# pure_midi.net
KiCad netlist of a schematic drawn in EAGLE
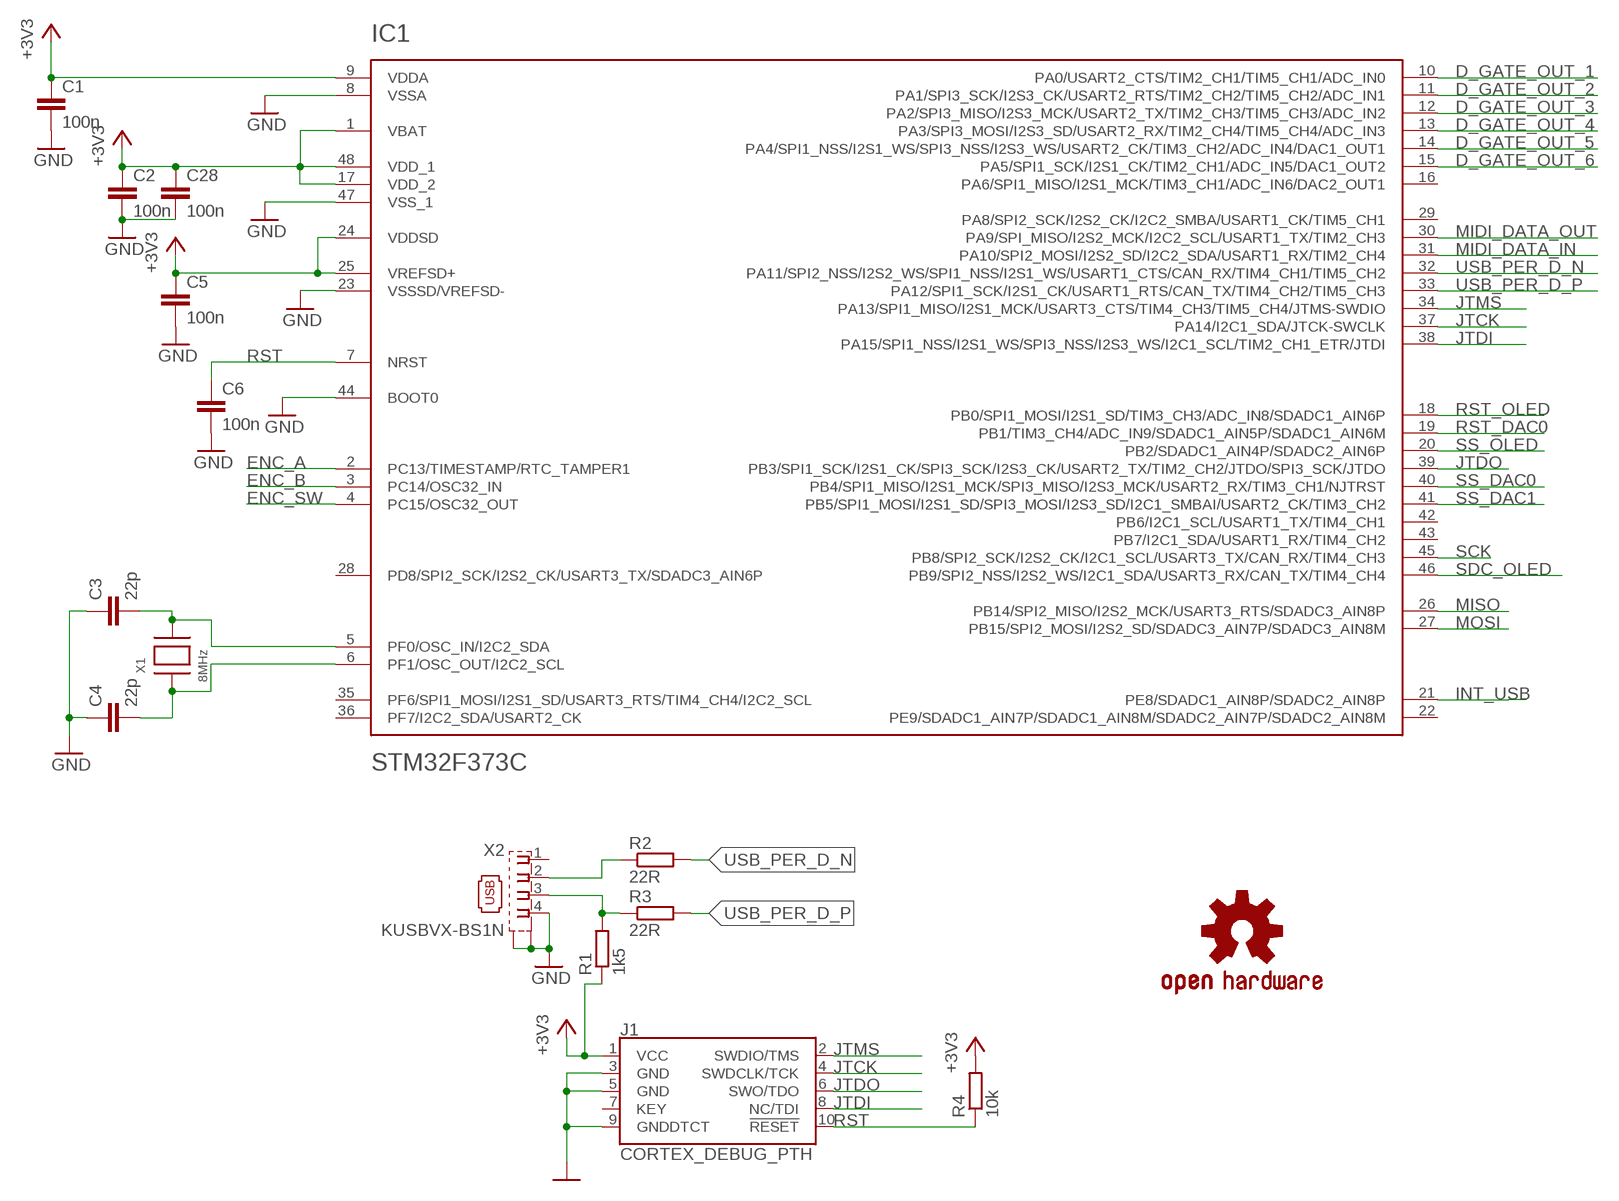
[diagram p0: schematic, sheet 1]
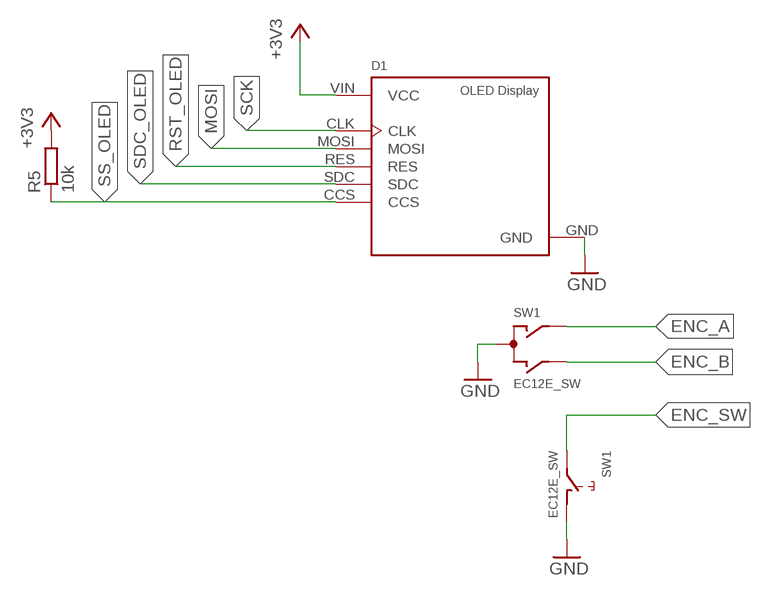
[diagram p1: schematic, sheet 2]
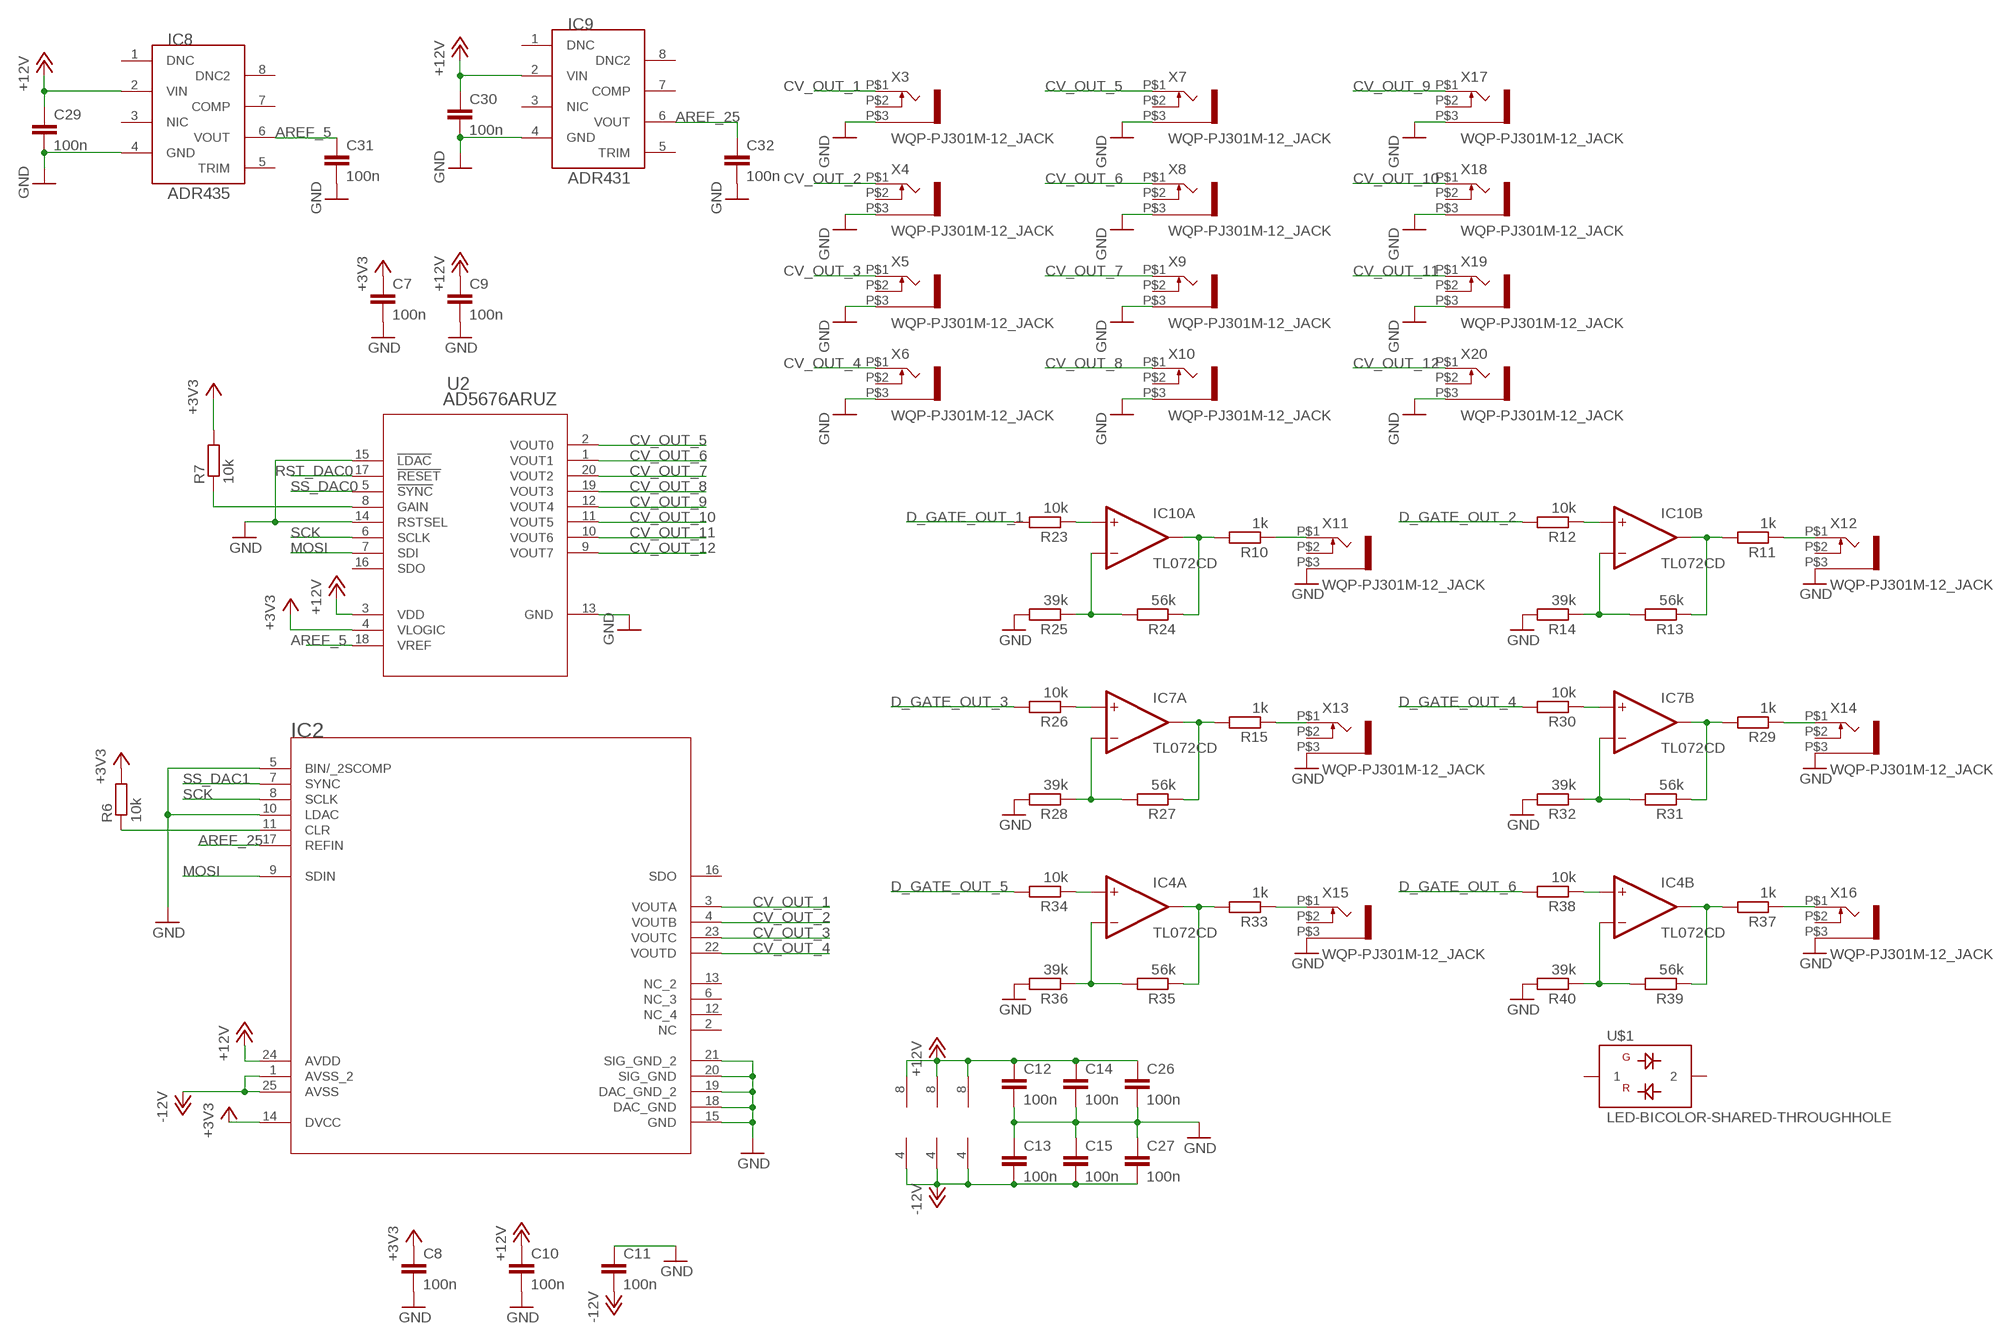
[diagram p2: schematic, sheet 3]
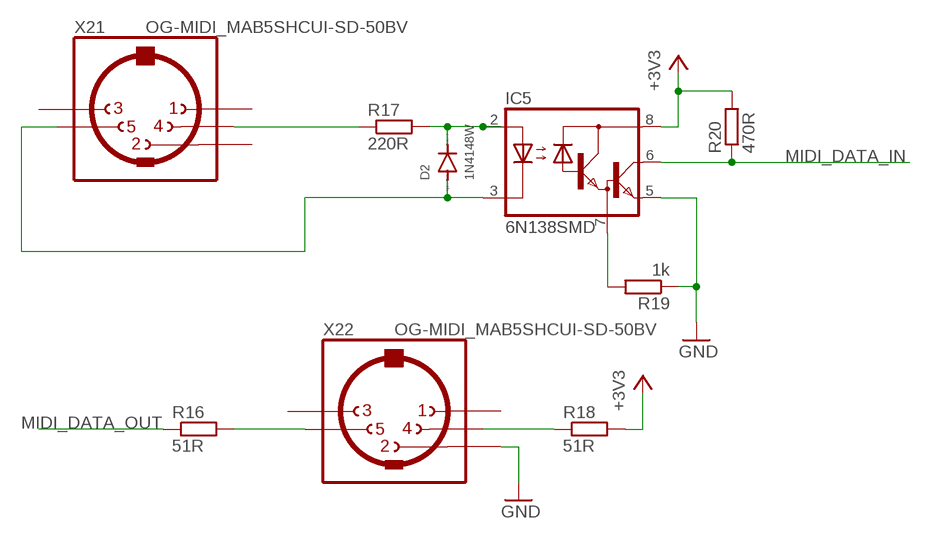
[diagram p3: schematic, sheet 4]
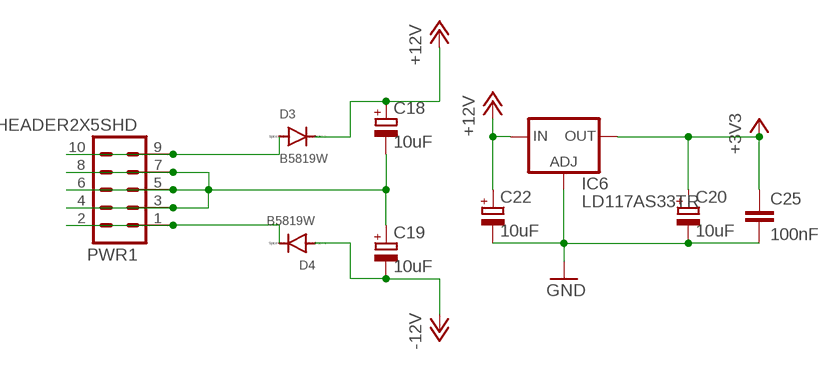
[diagram p4: schematic, sheet 5]

(export (version "E")
  (design (tool "Eeschema 10.0.6"))
  (components
    (comp (ref "C7")
      (value "100n")
      (footprint "eagle-import:C0603")
      (libsource (lib "eagle-import") (part "C-EUC0603"))
    )
    (comp (ref "C8")
      (value "100n")
      (footprint "eagle-import:C0603")
      (libsource (lib "eagle-import") (part "C-EUC0603"))
    )
    (comp (ref "C9")
      (value "100n")
      (footprint "eagle-import:C0603")
      (libsource (lib "eagle-import") (part "C-EUC0603"))
    )
    (comp (ref "C10")
      (value "100n")
      (footprint "eagle-import:C0603")
      (libsource (lib "eagle-import") (part "C-EUC0603"))
    )
    (comp (ref "C11")
      (value "100n")
      (footprint "eagle-import:C0603")
      (libsource (lib "eagle-import") (part "C-EUC0603"))
    )
    (comp (ref "C12")
      (value "100n")
      (footprint "eagle-import:C0603")
      (libsource (lib "eagle-import") (part "C-EUC0603"))
    )
    (comp (ref "C13")
      (value "100n")
      (footprint "eagle-import:C0603")
      (libsource (lib "eagle-import") (part "C-EUC0603"))
    )
    (comp (ref "C14")
      (value "100n")
      (footprint "eagle-import:C0603")
      (libsource (lib "eagle-import") (part "C-EUC0603"))
    )
    (comp (ref "C15")
      (value "100n")
      (footprint "eagle-import:C0603")
      (libsource (lib "eagle-import") (part "C-EUC0603"))
    )
    (comp (ref "C26")
      (value "100n")
      (footprint "eagle-import:C0603")
      (libsource (lib "eagle-import") (part "C-EUC0603"))
    )
    (comp (ref "C27")
      (value "100n")
      (footprint "eagle-import:C0603")
      (libsource (lib "eagle-import") (part "C-EUC0603"))
    )
    (comp (ref "C29")
      (value "100n")
      (footprint "eagle-import:C0603")
      (libsource (lib "eagle-import") (part "C-EUC0603"))
    )
    (comp (ref "C30")
      (value "100n")
      (footprint "eagle-import:C0603")
      (libsource (lib "eagle-import") (part "C-EUC0603"))
    )
    (comp (ref "C31")
      (value "100n")
      (footprint "eagle-import:C0603")
      (libsource (lib "eagle-import") (part "C-EUC0603"))
    )
    (comp (ref "C32")
      (value "100n")
      (footprint "eagle-import:C0603")
      (libsource (lib "eagle-import") (part "C-EUC0603"))
    )
    (comp (ref "IC2")
      (value "AD5754BREZ")
      (footprint "eagle-import:RE_24")
      (libsource (lib "eagle-import") (part "AD5754BREZ"))
    )
    (comp (ref "IC4")
      (value "TL072CD")
      (footprint "eagle-import:SOIC8")
      (libsource (lib "eagle-import") (part "TL072DC"))
    )
    (comp (ref "IC7")
      (value "TL072CD")
      (footprint "eagle-import:SOIC8")
      (libsource (lib "eagle-import") (part "TL072DC"))
    )
    (comp (ref "IC8")
      (value "ADR435")
      (footprint "eagle-import:MSOP8")
      (libsource (lib "eagle-import") (part "ADR43XXRMZ"))
    )
    (comp (ref "IC9")
      (value "ADR431")
      (footprint "eagle-import:MSOP8")
      (libsource (lib "eagle-import") (part "ADR43XXRMZ"))
    )
    (comp (ref "IC10")
      (value "TL072CD")
      (footprint "eagle-import:SOIC8")
      (libsource (lib "eagle-import") (part "TL072DC"))
    )
    (comp (ref "R6")
      (value "10k")
      (footprint "eagle-import:R0603")
      (libsource (lib "eagle-import") (part "R-EU_R0603"))
    )
    (comp (ref "R7")
      (value "10k")
      (footprint "eagle-import:R0603")
      (libsource (lib "eagle-import") (part "R-EU_R0603"))
    )
    (comp (ref "R10")
      (value "1k")
      (footprint "eagle-import:R0603")
      (libsource (lib "eagle-import") (part "R-EU_R0603"))
    )
    (comp (ref "R11")
      (value "1k")
      (footprint "eagle-import:R0603")
      (libsource (lib "eagle-import") (part "R-EU_R0603"))
    )
    (comp (ref "R12")
      (value "10k")
      (footprint "eagle-import:R0603")
      (libsource (lib "eagle-import") (part "R-EU_R0603"))
    )
    (comp (ref "R13")
      (value "56k")
      (footprint "eagle-import:R0603")
      (libsource (lib "eagle-import") (part "R-EU_R0603"))
    )
    (comp (ref "R14")
      (value "39k")
      (footprint "eagle-import:R0603")
      (libsource (lib "eagle-import") (part "R-EU_R0603"))
    )
    (comp (ref "R15")
      (value "1k")
      (footprint "eagle-import:R0603")
      (libsource (lib "eagle-import") (part "R-EU_R0603"))
    )
    (comp (ref "R23")
      (value "10k")
      (footprint "eagle-import:R0603")
      (libsource (lib "eagle-import") (part "R-EU_R0603"))
    )
    (comp (ref "R24")
      (value "56k")
      (footprint "eagle-import:R0603")
      (libsource (lib "eagle-import") (part "R-EU_R0603"))
    )
    (comp (ref "R25")
      (value "39k")
      (footprint "eagle-import:R0603")
      (libsource (lib "eagle-import") (part "R-EU_R0603"))
    )
    (comp (ref "R26")
      (value "10k")
      (footprint "eagle-import:R0603")
      (libsource (lib "eagle-import") (part "R-EU_R0603"))
    )
    (comp (ref "R27")
      (value "56k")
      (footprint "eagle-import:R0603")
      (libsource (lib "eagle-import") (part "R-EU_R0603"))
    )
    (comp (ref "R28")
      (value "39k")
      (footprint "eagle-import:R0603")
      (libsource (lib "eagle-import") (part "R-EU_R0603"))
    )
    (comp (ref "R29")
      (value "1k")
      (footprint "eagle-import:R0603")
      (libsource (lib "eagle-import") (part "R-EU_R0603"))
    )
    (comp (ref "R30")
      (value "10k")
      (footprint "eagle-import:R0603")
      (libsource (lib "eagle-import") (part "R-EU_R0603"))
    )
    (comp (ref "R31")
      (value "56k")
      (footprint "eagle-import:R0603")
      (libsource (lib "eagle-import") (part "R-EU_R0603"))
    )
    (comp (ref "R32")
      (value "39k")
      (footprint "eagle-import:R0603")
      (libsource (lib "eagle-import") (part "R-EU_R0603"))
    )
    (comp (ref "R33")
      (value "1k")
      (footprint "eagle-import:R0603")
      (libsource (lib "eagle-import") (part "R-EU_R0603"))
    )
    (comp (ref "R34")
      (value "10k")
      (footprint "eagle-import:R0603")
      (libsource (lib "eagle-import") (part "R-EU_R0603"))
    )
    (comp (ref "R35")
      (value "56k")
      (footprint "eagle-import:R0603")
      (libsource (lib "eagle-import") (part "R-EU_R0603"))
    )
    (comp (ref "R36")
      (value "39k")
      (footprint "eagle-import:R0603")
      (libsource (lib "eagle-import") (part "R-EU_R0603"))
    )
    (comp (ref "R37")
      (value "1k")
      (footprint "eagle-import:R0603")
      (libsource (lib "eagle-import") (part "R-EU_R0603"))
    )
    (comp (ref "R38")
      (value "10k")
      (footprint "eagle-import:R0603")
      (libsource (lib "eagle-import") (part "R-EU_R0603"))
    )
    (comp (ref "R39")
      (value "56k")
      (footprint "eagle-import:R0603")
      (libsource (lib "eagle-import") (part "R-EU_R0603"))
    )
    (comp (ref "R40")
      (value "39k")
      (footprint "eagle-import:R0603")
      (libsource (lib "eagle-import") (part "R-EU_R0603"))
    )
    (comp (ref "U$1")
      (value "LED-BICOLOR-SHARED-THROUGHHOLE")
      (footprint "eagle-import:LED3MM")
      (libsource (lib "eagle-import") (part "LED-BICOLOR-SHARED-THROUGHHOLE"))
    )
    (comp (ref "U2")
      (value "AD5676ARUZ")
      (footprint "eagle-import:RU_20")
      (libsource (lib "eagle-import") (part "AD5676ARUZ"))
    )
    (comp (ref "X3")
      (value "WQP-PJ301M-12_JACK")
      (footprint "eagle-import:WQP-PJ301M-12_JACK")
      (libsource (lib "eagle-import") (part "WQP-PJ301M-12_JACK"))
    )
    (comp (ref "X4")
      (value "WQP-PJ301M-12_JACK")
      (footprint "eagle-import:WQP-PJ301M-12_JACK")
      (libsource (lib "eagle-import") (part "WQP-PJ301M-12_JACK"))
    )
    (comp (ref "X5")
      (value "WQP-PJ301M-12_JACK")
      (footprint "eagle-import:WQP-PJ301M-12_JACK")
      (libsource (lib "eagle-import") (part "WQP-PJ301M-12_JACK"))
    )
    (comp (ref "X6")
      (value "WQP-PJ301M-12_JACK")
      (footprint "eagle-import:WQP-PJ301M-12_JACK")
      (libsource (lib "eagle-import") (part "WQP-PJ301M-12_JACK"))
    )
    (comp (ref "X7")
      (value "WQP-PJ301M-12_JACK")
      (footprint "eagle-import:WQP-PJ301M-12_JACK")
      (libsource (lib "eagle-import") (part "WQP-PJ301M-12_JACK"))
    )
    (comp (ref "X8")
      (value "WQP-PJ301M-12_JACK")
      (footprint "eagle-import:WQP-PJ301M-12_JACK")
      (libsource (lib "eagle-import") (part "WQP-PJ301M-12_JACK"))
    )
    (comp (ref "X9")
      (value "WQP-PJ301M-12_JACK")
      (footprint "eagle-import:WQP-PJ301M-12_JACK")
      (libsource (lib "eagle-import") (part "WQP-PJ301M-12_JACK"))
    )
    (comp (ref "X10")
      (value "WQP-PJ301M-12_JACK")
      (footprint "eagle-import:WQP-PJ301M-12_JACK")
      (libsource (lib "eagle-import") (part "WQP-PJ301M-12_JACK"))
    )
    (comp (ref "X11")
      (value "WQP-PJ301M-12_JACK")
      (footprint "eagle-import:WQP-PJ301M-12_JACK")
      (libsource (lib "eagle-import") (part "WQP-PJ301M-12_JACK"))
    )
    (comp (ref "X12")
      (value "WQP-PJ301M-12_JACK")
      (footprint "eagle-import:WQP-PJ301M-12_JACK")
      (libsource (lib "eagle-import") (part "WQP-PJ301M-12_JACK"))
    )
    (comp (ref "X13")
      (value "WQP-PJ301M-12_JACK")
      (footprint "eagle-import:WQP-PJ301M-12_JACK")
      (libsource (lib "eagle-import") (part "WQP-PJ301M-12_JACK"))
    )
    (comp (ref "X14")
      (value "WQP-PJ301M-12_JACK")
      (footprint "eagle-import:WQP-PJ301M-12_JACK")
      (libsource (lib "eagle-import") (part "WQP-PJ301M-12_JACK"))
    )
    (comp (ref "X15")
      (value "WQP-PJ301M-12_JACK")
      (footprint "eagle-import:WQP-PJ301M-12_JACK")
      (libsource (lib "eagle-import") (part "WQP-PJ301M-12_JACK"))
    )
    (comp (ref "X16")
      (value "WQP-PJ301M-12_JACK")
      (footprint "eagle-import:WQP-PJ301M-12_JACK")
      (libsource (lib "eagle-import") (part "WQP-PJ301M-12_JACK"))
    )
    (comp (ref "X17")
      (value "WQP-PJ301M-12_JACK")
      (footprint "eagle-import:WQP-PJ301M-12_JACK")
      (libsource (lib "eagle-import") (part "WQP-PJ301M-12_JACK"))
    )
    (comp (ref "X18")
      (value "WQP-PJ301M-12_JACK")
      (footprint "eagle-import:WQP-PJ301M-12_JACK")
      (libsource (lib "eagle-import") (part "WQP-PJ301M-12_JACK"))
    )
    (comp (ref "X19")
      (value "WQP-PJ301M-12_JACK")
      (footprint "eagle-import:WQP-PJ301M-12_JACK")
      (libsource (lib "eagle-import") (part "WQP-PJ301M-12_JACK"))
    )
    (comp (ref "X20")
      (value "WQP-PJ301M-12_JACK")
      (footprint "eagle-import:WQP-PJ301M-12_JACK")
      (libsource (lib "eagle-import") (part "WQP-PJ301M-12_JACK"))
    )
    (comp (ref "C1")
      (value "100n")
      (footprint "eagle-import:C0603")
      (libsource (lib "eagle-import") (part "C-EUC0603"))
    )
    (comp (ref "C2")
      (value "100n")
      (footprint "eagle-import:C0603")
      (libsource (lib "eagle-import") (part "C-EUC0603"))
    )
    (comp (ref "C3")
      (value "22p")
      (footprint "eagle-import:C0603")
      (libsource (lib "eagle-import") (part "C-EUC0603"))
    )
    (comp (ref "C4")
      (value "22p")
      (footprint "eagle-import:C0603")
      (libsource (lib "eagle-import") (part "C-EUC0603"))
    )
    (comp (ref "C5")
      (value "100n")
      (footprint "eagle-import:C0603")
      (libsource (lib "eagle-import") (part "C-EUC0603"))
    )
    (comp (ref "C6")
      (value "100n")
      (footprint "eagle-import:C0603")
      (libsource (lib "eagle-import") (part "C-EUC0603"))
    )
    (comp (ref "C28")
      (value "100n")
      (footprint "eagle-import:C0603")
      (libsource (lib "eagle-import") (part "C-EUC0603"))
    )
    (comp (ref "IC1")
      (value "STM32F373C")
      (footprint "eagle-import:LQFP48")
      (libsource (lib "eagle-import") (part "STM32F373C"))
    )
    (comp (ref "J1")
      (value "CORTEX_DEBUG_PTH")
      (footprint "eagle-import:2X5-PTH-1.27MM")
      (libsource (lib "eagle-import") (part "CORTEX_DEBUG_PTH"))
    )
    (comp (ref "LOGO1")
      (value "OSHW-LOGOM")
      (footprint "eagle-import:OSHW-LOGO-M")
      (libsource (lib "eagle-import") (part "OSHW-LOGOM"))
    )
    (comp (ref "R1")
      (value "1k5")
      (footprint "eagle-import:R0603")
      (libsource (lib "eagle-import") (part "R-EU_R0603"))
    )
    (comp (ref "R2")
      (value "22R")
      (footprint "eagle-import:R0603")
      (libsource (lib "eagle-import") (part "R-EU_R0603"))
    )
    (comp (ref "R3")
      (value "22R")
      (footprint "eagle-import:R0603")
      (libsource (lib "eagle-import") (part "R-EU_R0603"))
    )
    (comp (ref "R4")
      (value "10k")
      (footprint "eagle-import:R0603")
      (libsource (lib "eagle-import") (part "R-EU_R0603"))
    )
    (comp (ref "X1")
      (value "8MHz")
      (footprint "eagle-import:NX5032")
      (libsource (lib "eagle-import") (part "XTALNX5032"))
    )
    (comp (ref "X2")
      (value "KUSBVX-BS1N")
      (footprint "eagle-import:KUSBVX-BS1N")
      (libsource (lib "eagle-import") (part "KUSBVX-BS1N"))
    )
    (comp (ref "D2")
      (value "1N4148W")
      (footprint "eagle-import:SOD123")
      (libsource (lib "eagle-import") (part "DIODE-SOD123"))
    )
    (comp (ref "IC5")
      (value "6N138SMD")
      (footprint "eagle-import:SO8-GW300")
      (libsource (lib "eagle-import") (part "6N138SMD"))
    )
    (comp (ref "R16")
      (value "51R")
      (footprint "eagle-import:R0603")
      (libsource (lib "eagle-import") (part "R-EU_R0603"))
    )
    (comp (ref "R17")
      (value "220R")
      (footprint "eagle-import:R0603")
      (libsource (lib "eagle-import") (part "R-EU_R0603"))
    )
    (comp (ref "R18")
      (value "51R")
      (footprint "eagle-import:R0603")
      (libsource (lib "eagle-import") (part "R-EU_R0603"))
    )
    (comp (ref "R19")
      (value "1k")
      (footprint "eagle-import:R0603")
      (libsource (lib "eagle-import") (part "R-EU_R0603"))
    )
    (comp (ref "R20")
      (value "470R")
      (footprint "eagle-import:R0603")
      (libsource (lib "eagle-import") (part "R-EU_R0603"))
    )
    (comp (ref "X21")
      (value "OG-MIDI_MAB5SHCUI-SD-50BV")
      (footprint "eagle-import:OG-MIDI_SD-50BV")
      (libsource (lib "eagle-import") (part "OG-MIDI_MAB5SHCUI-SD-50BV"))
    )
    (comp (ref "X22")
      (value "OG-MIDI_MAB5SHCUI-SD-50BV")
      (footprint "eagle-import:OG-MIDI_SD-50BV")
      (libsource (lib "eagle-import") (part "OG-MIDI_MAB5SHCUI-SD-50BV"))
    )
    (comp (ref "D1")
      (value "OLED_1.3_128X64_SPI")
      (footprint "eagle-import:C1_ADAFRUIT_1.3_128X64_OLED")
      (libsource (lib "eagle-import") (part "OLED_1.3_128X64_SPI"))
    )
    (comp (ref "R5")
      (value "10k")
      (footprint "eagle-import:R0603")
      (libsource (lib "eagle-import") (part "R-EU_R0603"))
    )
    (comp (ref "SW1")
      (value "EC12E_SW")
      (footprint "eagle-import:ALPS_EC12E_SW")
      (fields (field (name "MPN") "EC12E2424407"))
      (libsource (lib "eagle-import") (part "EC12E_SW"))
    )
    (comp (ref "C18")
      (value "10uF")
      (footprint "eagle-import:CASE-A_3216")
      (libsource (lib "eagle-import") (part "CPOL-EUA/3216-18R"))
    )
    (comp (ref "C19")
      (value "10uF")
      (footprint "eagle-import:CASE-A_3216")
      (libsource (lib "eagle-import") (part "CPOL-EUA/3216-18R"))
    )
    (comp (ref "C20")
      (value "10uF")
      (footprint "eagle-import:CASE-A_3216")
      (libsource (lib "eagle-import") (part "CPOL-EUA/3216-18R"))
    )
    (comp (ref "C22")
      (value "10uF")
      (footprint "eagle-import:CASE-A_3216")
      (libsource (lib "eagle-import") (part "CPOL-EUA/3216-18R"))
    )
    (comp (ref "C25")
      (value "100nF")
      (footprint "eagle-import:C0603")
      (libsource (lib "eagle-import") (part "C-EUC0603"))
    )
    (comp (ref "D3")
      (value "B5819W")
      (footprint "eagle-import:SOD123")
      (libsource (lib "eagle-import") (part "DIODE-SOD123"))
    )
    (comp (ref "D4")
      (value "B5819W")
      (footprint "eagle-import:SOD123")
      (libsource (lib "eagle-import") (part "DIODE-SOD123"))
    )
    (comp (ref "IC6")
      (value "LD117AS33TR")
      (footprint "eagle-import:SOT223")
      (libsource (lib "eagle-import") (part "LD117A?S33TR"))
    )
    (comp (ref "PWR1")
      (value "HEADER2X5SHD")
      (footprint "eagle-import:2X5-SHROUDED")
      (libsource (lib "eagle-import") (part "HEADER2X5SHD"))
    )
  )
  (nets
    (net (code "1") (name "+3V3") (class "Default")
      (node (ref "C1") (pin "1") (pinfunction "1_1") (pintype "passive"))
      (node (ref "C2") (pin "1") (pinfunction "1_1") (pintype "passive"))
      (node (ref "C20") (pin "+") (pinfunction "+_+") (pintype "passive"))
      (node (ref "C25") (pin "1") (pinfunction "1_1") (pintype "passive"))
      (node (ref "C28") (pin "1") (pinfunction "1_1") (pintype "passive"))
      (node (ref "C5") (pin "1") (pinfunction "1_1") (pintype "passive"))
      (node (ref "C7") (pin "1") (pinfunction "1_1") (pintype "passive"))
      (node (ref "C8") (pin "1") (pinfunction "1_1") (pintype "passive"))
      (node (ref "D1") (pin "VIN") (pinfunction "VCC_VIN") (pintype "power_in"))
      (node (ref "IC1") (pin "1") (pinfunction "VBAT_1") (pintype "power_in"))
      (node (ref "IC1") (pin "17") (pinfunction "VDD_2_17") (pintype "power_in"))
      (node (ref "IC1") (pin "24") (pinfunction "VDDSD_24") (pintype "power_in"))
      (node (ref "IC1") (pin "25") (pinfunction "VREFSD+_25") (pintype "power_in"))
      (node (ref "IC1") (pin "48") (pinfunction "VDD_1_48") (pintype "power_in"))
      (node (ref "IC1") (pin "9") (pinfunction "VDDA_9") (pintype "power_in"))
      (node (ref "IC2") (pin "14") (pinfunction "DVCC_14") (pintype "power_in"))
      (node (ref "IC5") (pin "8") (pinfunction "VCC_8") (pintype "passive"))
      (node (ref "IC6") (pin "4") (pinfunction "OUT_4") (pintype "passive"))
      (node (ref "J1") (pin "1") (pinfunction "VCC_1") (pintype "bidirectional"))
      (node (ref "R1") (pin "1") (pinfunction "1_1") (pintype "passive"))
      (node (ref "R18") (pin "2") (pinfunction "2_2") (pintype "passive"))
      (node (ref "R20") (pin "2") (pinfunction "2_2") (pintype "passive"))
      (node (ref "R4") (pin "2") (pinfunction "2_2") (pintype "passive"))
      (node (ref "R5") (pin "2") (pinfunction "2_2") (pintype "passive"))
      (node (ref "R6") (pin "2") (pinfunction "2_2") (pintype "passive"))
      (node (ref "R7") (pin "2") (pinfunction "2_2") (pintype "passive"))
      (node (ref "U2") (pin "4") (pinfunction "VLOGIC_4") (pintype "passive"))
    )
    (net (code "2") (name "+12V") (class "Default")
      (node (ref "C10") (pin "1") (pinfunction "1_1") (pintype "passive"))
      (node (ref "C12") (pin "1") (pinfunction "1_1") (pintype "passive"))
      (node (ref "C14") (pin "1") (pinfunction "1_1") (pintype "passive"))
      (node (ref "C18") (pin "+") (pinfunction "+_+") (pintype "passive"))
      (node (ref "C22") (pin "+") (pinfunction "+_+") (pintype "passive"))
      (node (ref "C26") (pin "1") (pinfunction "1_1") (pintype "passive"))
      (node (ref "C29") (pin "1") (pinfunction "1_1") (pintype "passive"))
      (node (ref "C30") (pin "1") (pinfunction "1_1") (pintype "passive"))
      (node (ref "C9") (pin "1") (pinfunction "1_1") (pintype "passive"))
      (node (ref "D3") (pin "C") (pinfunction "C_C") (pintype "passive"))
      (node (ref "IC10") (pin "8") (pinfunction "V+_8") (pintype "power_in"))
      (node (ref "IC2") (pin "24") (pinfunction "AVDD_24") (pintype "power_in"))
      (node (ref "IC4") (pin "8") (pinfunction "V+_8") (pintype "power_in"))
      (node (ref "IC6") (pin "3") (pinfunction "IN_3") (pintype "input"))
      (node (ref "IC7") (pin "8") (pinfunction "V+_8") (pintype "power_in"))
      (node (ref "IC8") (pin "2") (pinfunction "VIN_2") (pintype "power_in"))
      (node (ref "IC9") (pin "2") (pinfunction "VIN_2") (pintype "power_in"))
      (node (ref "U2") (pin "3") (pinfunction "VDD_3") (pintype "passive"))
    )
    (net (code "3") (name "-12V") (class "Default")
      (node (ref "C11") (pin "2") (pinfunction "2_2") (pintype "passive"))
      (node (ref "C13") (pin "2") (pinfunction "2_2") (pintype "passive"))
      (node (ref "C15") (pin "2") (pinfunction "2_2") (pintype "passive"))
      (node (ref "C19") (pin "-") (pinfunction "-_-") (pintype "passive"))
      (node (ref "C27") (pin "2") (pinfunction "2_2") (pintype "passive"))
      (node (ref "D4") (pin "A") (pinfunction "A_A") (pintype "passive"))
      (node (ref "IC10") (pin "4") (pinfunction "V-_4") (pintype "power_in"))
      (node (ref "IC2") (pin "1") (pinfunction "AVSS_2_1") (pintype "passive"))
      (node (ref "IC2") (pin "25") (pinfunction "AVSS_25") (pintype "power_in"))
      (node (ref "IC4") (pin "4") (pinfunction "V-_4") (pintype "power_in"))
      (node (ref "IC7") (pin "4") (pinfunction "V-_4") (pintype "power_in"))
    )
    (net (code "4") (name "AREF_5") (class "Default")
      (node (ref "C31") (pin "1") (pinfunction "1_1") (pintype "passive"))
      (node (ref "IC8") (pin "6") (pinfunction "VOUT_6") (pintype "power_in"))
      (node (ref "U2") (pin "18") (pinfunction "VREF_18") (pintype "passive"))
    )
    (net (code "5") (name "AREF_25") (class "Default")
      (node (ref "C32") (pin "1") (pinfunction "1_1") (pintype "passive"))
      (node (ref "IC2") (pin "17") (pinfunction "REFIN_17") (pintype "passive"))
      (node (ref "IC9") (pin "6") (pinfunction "VOUT_6") (pintype "power_in"))
    )
    (net (code "6") (name "CV_OUT_1") (class "Default")
      (node (ref "IC2") (pin "3") (pinfunction "VOUTA_3") (pintype "passive"))
      (node (ref "X3") (pin "P$1") (pinfunction "2_P$1") (pintype "passive"))
    )
    (net (code "7") (name "CV_OUT_2") (class "Default")
      (node (ref "IC2") (pin "4") (pinfunction "VOUTB_4") (pintype "passive"))
      (node (ref "X4") (pin "P$1") (pinfunction "2_P$1") (pintype "passive"))
    )
    (net (code "8") (name "CV_OUT_3") (class "Default")
      (node (ref "IC2") (pin "23") (pinfunction "VOUTC_23") (pintype "passive"))
      (node (ref "X5") (pin "P$1") (pinfunction "2_P$1") (pintype "passive"))
    )
    (net (code "9") (name "CV_OUT_4") (class "Default")
      (node (ref "IC2") (pin "22") (pinfunction "VOUTD_22") (pintype "passive"))
      (node (ref "X6") (pin "P$1") (pinfunction "2_P$1") (pintype "passive"))
    )
    (net (code "10") (name "CV_OUT_5") (class "Default")
      (node (ref "U2") (pin "2") (pinfunction "VOUT0_2") (pintype "passive"))
      (node (ref "X7") (pin "P$1") (pinfunction "2_P$1") (pintype "passive"))
    )
    (net (code "11") (name "CV_OUT_6") (class "Default")
      (node (ref "U2") (pin "1") (pinfunction "VOUT1_1") (pintype "passive"))
      (node (ref "X8") (pin "P$1") (pinfunction "2_P$1") (pintype "passive"))
    )
    (net (code "12") (name "CV_OUT_7") (class "Default")
      (node (ref "U2") (pin "20") (pinfunction "VOUT2_20") (pintype "passive"))
      (node (ref "X9") (pin "P$1") (pinfunction "2_P$1") (pintype "passive"))
    )
    (net (code "13") (name "CV_OUT_8") (class "Default")
      (node (ref "U2") (pin "19") (pinfunction "VOUT3_19") (pintype "passive"))
      (node (ref "X10") (pin "P$1") (pinfunction "2_P$1") (pintype "passive"))
    )
    (net (code "14") (name "CV_OUT_9") (class "Default")
      (node (ref "U2") (pin "12") (pinfunction "VOUT4_12") (pintype "passive"))
      (node (ref "X17") (pin "P$1") (pinfunction "2_P$1") (pintype "passive"))
    )
    (net (code "15") (name "CV_OUT_10") (class "Default")
      (node (ref "U2") (pin "11") (pinfunction "VOUT5_11") (pintype "passive"))
      (node (ref "X18") (pin "P$1") (pinfunction "2_P$1") (pintype "passive"))
    )
    (net (code "16") (name "CV_OUT_11") (class "Default")
      (node (ref "U2") (pin "10") (pinfunction "VOUT6_10") (pintype "passive"))
      (node (ref "X19") (pin "P$1") (pinfunction "2_P$1") (pintype "passive"))
    )
    (net (code "17") (name "CV_OUT_12") (class "Default")
      (node (ref "U2") (pin "9") (pinfunction "VOUT7_9") (pintype "passive"))
      (node (ref "X20") (pin "P$1") (pinfunction "2_P$1") (pintype "passive"))
    )
    (net (code "18") (name "D_GATE_OUT_1") (class "Default")
      (node (ref "IC1") (pin "10") (pinfunction "PA0/USART2_CTS/TIM2_CH1/TIM5_CH1/ADC_IN0_10") (pintype "bidirectional"))
      (node (ref "R23") (pin "2") (pinfunction "2_2") (pintype "passive"))
    )
    (net (code "19") (name "D_GATE_OUT_2") (class "Default")
      (node (ref "IC1") (pin "11") (pinfunction "PA1/SPI3_SCK/I2S3_CK/USART2_RTS/TIM2_CH2/TIM5_CH2/ADC_IN1_11") (pintype "bidirectional"))
      (node (ref "R12") (pin "2") (pinfunction "2_2") (pintype "passive"))
    )
    (net (code "20") (name "D_GATE_OUT_3") (class "Default")
      (node (ref "IC1") (pin "12") (pinfunction "PA2/SPI3_MISO/I2S3_MCK/USART2_TX/TIM2_CH3/TIM5_CH3/ADC_IN2_12") (pintype "bidirectional"))
      (node (ref "R26") (pin "2") (pinfunction "2_2") (pintype "passive"))
    )
    (net (code "21") (name "D_GATE_OUT_4") (class "Default")
      (node (ref "IC1") (pin "13") (pinfunction "PA3/SPI3_MOSI/I2S3_SD/USART2_RX/TIM2_CH4/TIM5_CH4/ADC_IN3_13") (pintype "bidirectional"))
      (node (ref "R30") (pin "2") (pinfunction "2_2") (pintype "passive"))
    )
    (net (code "22") (name "D_GATE_OUT_5") (class "Default")
      (node (ref "IC1") (pin "14") (pinfunction "PA4/SPI1_NSS/I2S1_WS/SPI3_NSS/I2S3_WS/USART2_CK/TIM3_CH2/ADC_IN4/DAC1_OUT1_14") (pintype "bidirectional"))
      (node (ref "R34") (pin "2") (pinfunction "2_2") (pintype "passive"))
    )
    (net (code "23") (name "D_GATE_OUT_6") (class "Default")
      (node (ref "IC1") (pin "15") (pinfunction "PA5/SPI1_SCK/I2S1_CK/TIM2_CH1/ADC_IN5/DAC1_OUT2_15") (pintype "bidirectional"))
      (node (ref "R38") (pin "2") (pinfunction "2_2") (pintype "passive"))
    )
    (net (code "24") (name "ENC_A") (class "Default")
      (node (ref "IC1") (pin "2") (pinfunction "PC13/TIMESTAMP/RTC_TAMPER1_2") (pintype "bidirectional"))
      (node (ref "SW1") (pin "A") (pinfunction "A_A") (pintype "passive"))
    )
    (net (code "25") (name "ENC_B") (class "Default")
      (node (ref "IC1") (pin "3") (pinfunction "PC14/OSC32_IN_3") (pintype "bidirectional"))
      (node (ref "SW1") (pin "B") (pinfunction "B_B") (pintype "passive"))
    )
    (net (code "26") (name "ENC_SW") (class "Default")
      (node (ref "IC1") (pin "4") (pinfunction "PC15/OSC32_OUT_4") (pintype "bidirectional"))
      (node (ref "SW1") (pin "E") (pinfunction "2_E") (pintype "passive"))
    )
    (net (code "27") (name "GND") (class "Default")
      (node (ref "C1") (pin "2") (pinfunction "2_2") (pintype "passive"))
      (node (ref "C10") (pin "2") (pinfunction "2_2") (pintype "passive"))
      (node (ref "C11") (pin "1") (pinfunction "1_1") (pintype "passive"))
      (node (ref "C12") (pin "2") (pinfunction "2_2") (pintype "passive"))
      (node (ref "C13") (pin "1") (pinfunction "1_1") (pintype "passive"))
      (node (ref "C14") (pin "2") (pinfunction "2_2") (pintype "passive"))
      (node (ref "C15") (pin "1") (pinfunction "1_1") (pintype "passive"))
      (node (ref "C2") (pin "2") (pinfunction "2_2") (pintype "passive"))
      (node (ref "C20") (pin "-") (pinfunction "-_-") (pintype "passive"))
      (node (ref "C22") (pin "-") (pinfunction "-_-") (pintype "passive"))
      (node (ref "C25") (pin "2") (pinfunction "2_2") (pintype "passive"))
      (node (ref "C26") (pin "2") (pinfunction "2_2") (pintype "passive"))
      (node (ref "C27") (pin "1") (pinfunction "1_1") (pintype "passive"))
      (node (ref "C28") (pin "2") (pinfunction "2_2") (pintype "passive"))
      (node (ref "C29") (pin "2") (pinfunction "2_2") (pintype "passive"))
      (node (ref "C3") (pin "1") (pinfunction "1_1") (pintype "passive"))
      (node (ref "C30") (pin "2") (pinfunction "2_2") (pintype "passive"))
      (node (ref "C31") (pin "2") (pinfunction "2_2") (pintype "passive"))
      (node (ref "C32") (pin "2") (pinfunction "2_2") (pintype "passive"))
      (node (ref "C4") (pin "1") (pinfunction "1_1") (pintype "passive"))
      (node (ref "C5") (pin "2") (pinfunction "2_2") (pintype "passive"))
      (node (ref "C6") (pin "2") (pinfunction "2_2") (pintype "passive"))
      (node (ref "C7") (pin "2") (pinfunction "2_2") (pintype "passive"))
      (node (ref "C8") (pin "2") (pinfunction "2_2") (pintype "passive"))
      (node (ref "C9") (pin "2") (pinfunction "2_2") (pintype "passive"))
      (node (ref "D1") (pin "GND") (pinfunction "GND_GND") (pintype "power_in"))
      (node (ref "IC1") (pin "23") (pinfunction "VSSSD/VREFSD-_23") (pintype "power_in"))
      (node (ref "IC1") (pin "44") (pinfunction "BOOT0_44") (pintype "bidirectional"))
      (node (ref "IC1") (pin "47") (pinfunction "VSS_1_47") (pintype "power_in"))
      (node (ref "IC1") (pin "8") (pinfunction "VSSA_8") (pintype "power_in"))
      (node (ref "IC2") (pin "10") (pinfunction "LDAC_10") (pintype "passive"))
      (node (ref "IC2") (pin "15") (pinfunction "GND_15") (pintype "passive"))
      (node (ref "IC2") (pin "18") (pinfunction "DAC_GND_18") (pintype "passive"))
      (node (ref "IC2") (pin "19") (pinfunction "DAC_GND_2_19") (pintype "passive"))
      (node (ref "IC2") (pin "20") (pinfunction "SIG_GND_20") (pintype "passive"))
      (node (ref "IC2") (pin "21") (pinfunction "SIG_GND_2_21") (pintype "passive"))
      (node (ref "IC2") (pin "5") (pinfunction "BIN/_2SCOMP_5") (pintype "passive"))
      (node (ref "IC5") (pin "5") (pinfunction "GND_5") (pintype "passive"))
      (node (ref "IC6") (pin "1") (pinfunction "ADJ_1") (pintype "input"))
      (node (ref "IC8") (pin "4") (pinfunction "GND_4") (pintype "power_in"))
      (node (ref "IC9") (pin "4") (pinfunction "GND_4") (pintype "power_in"))
      (node (ref "J1") (pin "3") (pinfunction "GND_3") (pintype "bidirectional"))
      (node (ref "J1") (pin "5") (pinfunction "GND_5") (pintype "bidirectional"))
      (node (ref "J1") (pin "9") (pinfunction "GNDDTCT_9") (pintype "bidirectional"))
      (node (ref "R14") (pin "2") (pinfunction "2_2") (pintype "passive"))
      (node (ref "R19") (pin "1") (pinfunction "1_1") (pintype "passive"))
      (node (ref "R25") (pin "2") (pinfunction "2_2") (pintype "passive"))
      (node (ref "R28") (pin "2") (pinfunction "2_2") (pintype "passive"))
      (node (ref "R32") (pin "2") (pinfunction "2_2") (pintype "passive"))
      (node (ref "R36") (pin "2") (pinfunction "2_2") (pintype "passive"))
      (node (ref "R40") (pin "2") (pinfunction "2_2") (pintype "passive"))
      (node (ref "SW1") (pin "C") (pinfunction "C_C") (pintype "passive"))
      (node (ref "SW1") (pin "D") (pinfunction "1_D") (pintype "passive"))
      (node (ref "U2") (pin "13") (pinfunction "GND_13") (pintype "passive"))
      (node (ref "U2") (pin "14") (pinfunction "RSTSEL_14") (pintype "passive"))
      (node (ref "U2") (pin "15") (pinfunction "~{LDAC}_15") (pintype "passive"))
      (node (ref "X10") (pin "P$3") (pinfunction "1_P$3") (pintype "passive"))
      (node (ref "X11") (pin "P$3") (pinfunction "1_P$3") (pintype "passive"))
      (node (ref "X12") (pin "P$3") (pinfunction "1_P$3") (pintype "passive"))
      (node (ref "X13") (pin "P$3") (pinfunction "1_P$3") (pintype "passive"))
      (node (ref "X14") (pin "P$3") (pinfunction "1_P$3") (pintype "passive"))
      (node (ref "X15") (pin "P$3") (pinfunction "1_P$3") (pintype "passive"))
      (node (ref "X16") (pin "P$3") (pinfunction "1_P$3") (pintype "passive"))
      (node (ref "X17") (pin "P$3") (pinfunction "1_P$3") (pintype "passive"))
      (node (ref "X18") (pin "P$3") (pinfunction "1_P$3") (pintype "passive"))
      (node (ref "X19") (pin "P$3") (pinfunction "1_P$3") (pintype "passive"))
      (node (ref "X2") (pin "4") (pinfunction "4_4") (pintype "passive"))
      (node (ref "X2") (pin "M1") (pinfunction "S1_M1") (pintype "passive"))
      (node (ref "X2") (pin "M2") (pinfunction "S2_M2") (pintype "passive"))
      (node (ref "X20") (pin "P$3") (pinfunction "1_P$3") (pintype "passive"))
      (node (ref "X22") (pin "2") (pinfunction "2_2") (pintype "passive"))
      (node (ref "X3") (pin "P$3") (pinfunction "1_P$3") (pintype "passive"))
      (node (ref "X4") (pin "P$3") (pinfunction "1_P$3") (pintype "passive"))
      (node (ref "X5") (pin "P$3") (pinfunction "1_P$3") (pintype "passive"))
      (node (ref "X6") (pin "P$3") (pinfunction "1_P$3") (pintype "passive"))
      (node (ref "X7") (pin "P$3") (pinfunction "1_P$3") (pintype "passive"))
      (node (ref "X8") (pin "P$3") (pinfunction "1_P$3") (pintype "passive"))
      (node (ref "X9") (pin "P$3") (pinfunction "1_P$3") (pintype "passive"))
    )
    (net (code "28") (name "INT_USB") (class "Default")
      (node (ref "IC1") (pin "21") (pinfunction "PE8/SDADC1_AIN8P/SDADC2_AIN8P_21") (pintype "bidirectional"))
    )
    (net (code "29") (name "JTCK") (class "Default")
      (node (ref "IC1") (pin "37") (pinfunction "PA14/I2C1_SDA/JTCK-SWCLK_37") (pintype "bidirectional"))
      (node (ref "J1") (pin "4") (pinfunction "SWDCLK/TCK_4") (pintype "bidirectional"))
    )
    (net (code "30") (name "JTDI") (class "Default")
      (node (ref "IC1") (pin "38") (pinfunction "PA15/SPI1_NSS/I2S1_WS/SPI3_NSS/I2S3_WS/I2C1_SCL/TIM2_CH1_ETR/JTDI_38") (pintype "bidirectional"))
      (node (ref "J1") (pin "8") (pinfunction "NC/TDI_8") (pintype "bidirectional"))
    )
    (net (code "31") (name "JTDO") (class "Default")
      (node (ref "IC1") (pin "39") (pinfunction "PB3/SPI1_SCK/I2S1_CK/SPI3_SCK/I2S3_CK/USART2_TX/TIM2_CH2/JTDO/SPI3_SCK/JTDO_39") (pintype "bidirectional"))
      (node (ref "J1") (pin "6") (pinfunction "SWO/TDO_6") (pintype "bidirectional"))
    )
    (net (code "32") (name "JTMS") (class "Default")
      (node (ref "IC1") (pin "34") (pinfunction "PA13/SPI1_MISO/I2S1_MCK/USART3_CTS/TIM4_CH3/TIM5_CH4/JTMS-SWDIO_34") (pintype "bidirectional"))
      (node (ref "J1") (pin "2") (pinfunction "SWDIO/TMS_2") (pintype "bidirectional"))
    )
    (net (code "33") (name "MIDI_DATA_IN") (class "Default")
      (node (ref "IC1") (pin "31") (pinfunction "PA10/SPI2_MOSI/I2S2_SD/I2C2_SDA/USART1_RX/TIM2_CH4_31") (pintype "bidirectional"))
      (node (ref "IC5") (pin "6") (pinfunction "VO_6") (pintype "passive"))
      (node (ref "R20") (pin "1") (pinfunction "1_1") (pintype "passive"))
    )
    (net (code "34") (name "MIDI_DATA_OUT") (class "Default")
      (node (ref "IC1") (pin "30") (pinfunction "PA9/SPI_MISO/I2S2_MCK/I2C2_SCL/USART1_TX/TIM2_CH3_30") (pintype "bidirectional"))
      (node (ref "R16") (pin "1") (pinfunction "1_1") (pintype "passive"))
    )
    (net (code "35") (name "MISO") (class "Default")
      (node (ref "IC1") (pin "26") (pinfunction "PB14/SPI2_MISO/I2S2_MCK/USART3_RTS/SDADC3_AIN8P_26") (pintype "bidirectional"))
    )
    (net (code "36") (name "MOSI") (class "Default")
      (node (ref "D1") (pin "MOSI") (pinfunction "MOSI_MOSI") (pintype "input"))
      (node (ref "IC1") (pin "27") (pinfunction "PB15/SPI2_MOSI/I2S2_SD/SDADC3_AIN7P/SDADC3_AIN8M_27") (pintype "bidirectional"))
      (node (ref "IC2") (pin "9") (pinfunction "SDIN_9") (pintype "passive"))
      (node (ref "U2") (pin "7") (pinfunction "SDI_7") (pintype "passive"))
    )
    (net (code "37") (name "Net-(C18-Pad-)") (class "Default")
      (node (ref "C18") (pin "-") (pinfunction "-_-") (pintype "passive"))
      (node (ref "C19") (pin "+") (pinfunction "+_+") (pintype "passive"))
      (node (ref "PWR1") (pin "3") (pinfunction "3_3") (pintype "passive"))
      (node (ref "PWR1") (pin "4") (pinfunction "4_4") (pintype "passive"))
      (node (ref "PWR1") (pin "5") (pinfunction "5_5") (pintype "passive"))
      (node (ref "PWR1") (pin "6") (pinfunction "6_6") (pintype "passive"))
      (node (ref "PWR1") (pin "7") (pinfunction "7_7") (pintype "passive"))
      (node (ref "PWR1") (pin "8") (pinfunction "8_8") (pintype "passive"))
    )
    (net (code "38") (name "Net-(D3-PadA)") (class "Default")
      (node (ref "D3") (pin "A") (pinfunction "A_A") (pintype "passive"))
      (node (ref "PWR1") (pin "10") (pinfunction "10_10") (pintype "passive"))
      (node (ref "PWR1") (pin "9") (pinfunction "9_9") (pintype "passive"))
    )
    (net (code "39") (name "Net-(D4-PadC)") (class "Default")
      (node (ref "D4") (pin "C") (pinfunction "C_C") (pintype "passive"))
      (node (ref "PWR1") (pin "1") (pinfunction "1_1") (pintype "passive"))
      (node (ref "PWR1") (pin "2") (pinfunction "2_2") (pintype "passive"))
    )
    (net (code "40") (name "Net-(IC1-PF0{slash}OSC_IN{slash}I2C2_SDA)") (class "Default")
      (node (ref "C3") (pin "2") (pinfunction "2_2") (pintype "passive"))
      (node (ref "IC1") (pin "5") (pinfunction "PF0/OSC_IN/I2C2_SDA_5") (pintype "bidirectional"))
      (node (ref "X1") (pin "P$2") (pinfunction "P$2_P$2") (pintype "bidirectional"))
    )
    (net (code "41") (name "Net-(IC1-PF1{slash}OSC_OUT{slash}I2C2_SCL)") (class "Default")
      (node (ref "C4") (pin "2") (pinfunction "2_2") (pintype "passive"))
      (node (ref "IC1") (pin "6") (pinfunction "PF1/OSC_OUT/I2C2_SCL_6") (pintype "bidirectional"))
      (node (ref "X1") (pin "P$1") (pinfunction "P$1_P$1") (pintype "bidirectional"))
    )
    (net (code "42") (name "Net-(IC2-CLR)") (class "Default")
      (node (ref "IC2") (pin "11") (pinfunction "CLR_11") (pintype "passive"))
      (node (ref "R6") (pin "1") (pinfunction "1_1") (pintype "passive"))
    )
    (net (code "43") (name "Net-(IC4A-+IN)") (class "Default")
      (node (ref "IC4") (pin "3") (pinfunction "+IN_3") (pintype "input"))
      (node (ref "R34") (pin "1") (pinfunction "1_1") (pintype "passive"))
    )
    (net (code "44") (name "Net-(IC4A--IN)") (class "Default")
      (node (ref "IC4") (pin "2") (pinfunction "-IN_2") (pintype "input"))
      (node (ref "R35") (pin "2") (pinfunction "2_2") (pintype "passive"))
      (node (ref "R36") (pin "1") (pinfunction "1_1") (pintype "passive"))
    )
    (net (code "45") (name "Net-(IC4A-OUT)") (class "Default")
      (node (ref "IC4") (pin "1") (pinfunction "OUT_1") (pintype "output"))
      (node (ref "R33") (pin "2") (pinfunction "2_2") (pintype "passive"))
      (node (ref "R35") (pin "1") (pinfunction "1_1") (pintype "passive"))
    )
    (net (code "46") (name "Net-(IC4B-+IN)") (class "Default")
      (node (ref "IC4") (pin "5") (pinfunction "+IN_5") (pintype "input"))
      (node (ref "R38") (pin "1") (pinfunction "1_1") (pintype "passive"))
    )
    (net (code "47") (name "Net-(IC4B--IN)") (class "Default")
      (node (ref "IC4") (pin "6") (pinfunction "-IN_6") (pintype "input"))
      (node (ref "R39") (pin "2") (pinfunction "2_2") (pintype "passive"))
      (node (ref "R40") (pin "1") (pinfunction "1_1") (pintype "passive"))
    )
    (net (code "48") (name "Net-(IC4B-OUT)") (class "Default")
      (node (ref "IC4") (pin "7") (pinfunction "OUT_7") (pintype "output"))
      (node (ref "R37") (pin "2") (pinfunction "2_2") (pintype "passive"))
      (node (ref "R39") (pin "1") (pinfunction "1_1") (pintype "passive"))
    )
    (net (code "49") (name "Net-(IC5-A)") (class "Default")
      (node (ref "D2") (pin "C") (pinfunction "C_C") (pintype "passive"))
      (node (ref "IC5") (pin "2") (pinfunction "A_2") (pintype "passive"))
      (node (ref "R17") (pin "2") (pinfunction "2_2") (pintype "passive"))
    )
    (net (code "50") (name "Net-(IC5-C)") (class "Default")
      (node (ref "D2") (pin "A") (pinfunction "A_A") (pintype "passive"))
      (node (ref "IC5") (pin "3") (pinfunction "C_3") (pintype "passive"))
      (node (ref "X21") (pin "5") (pinfunction "5_5") (pintype "passive"))
    )
    (net (code "51") (name "Net-(IC5-VB)") (class "Default")
      (node (ref "IC5") (pin "7") (pinfunction "VB_7") (pintype "passive"))
      (node (ref "R19") (pin "2") (pinfunction "2_2") (pintype "passive"))
    )
    (net (code "52") (name "Net-(IC7A-+IN)") (class "Default")
      (node (ref "IC7") (pin "3") (pinfunction "+IN_3") (pintype "input"))
      (node (ref "R26") (pin "1") (pinfunction "1_1") (pintype "passive"))
    )
    (net (code "53") (name "Net-(IC7A--IN)") (class "Default")
      (node (ref "IC7") (pin "2") (pinfunction "-IN_2") (pintype "input"))
      (node (ref "R27") (pin "2") (pinfunction "2_2") (pintype "passive"))
      (node (ref "R28") (pin "1") (pinfunction "1_1") (pintype "passive"))
    )
    (net (code "54") (name "Net-(IC7A-OUT)") (class "Default")
      (node (ref "IC7") (pin "1") (pinfunction "OUT_1") (pintype "output"))
      (node (ref "R15") (pin "2") (pinfunction "2_2") (pintype "passive"))
      (node (ref "R27") (pin "1") (pinfunction "1_1") (pintype "passive"))
    )
    (net (code "55") (name "Net-(IC7B-+IN)") (class "Default")
      (node (ref "IC7") (pin "5") (pinfunction "+IN_5") (pintype "input"))
      (node (ref "R30") (pin "1") (pinfunction "1_1") (pintype "passive"))
    )
    (net (code "56") (name "Net-(IC7B--IN)") (class "Default")
      (node (ref "IC7") (pin "6") (pinfunction "-IN_6") (pintype "input"))
      (node (ref "R31") (pin "2") (pinfunction "2_2") (pintype "passive"))
      (node (ref "R32") (pin "1") (pinfunction "1_1") (pintype "passive"))
    )
    (net (code "57") (name "Net-(IC7B-OUT)") (class "Default")
      (node (ref "IC7") (pin "7") (pinfunction "OUT_7") (pintype "output"))
      (node (ref "R29") (pin "2") (pinfunction "2_2") (pintype "passive"))
      (node (ref "R31") (pin "1") (pinfunction "1_1") (pintype "passive"))
    )
    (net (code "58") (name "Net-(IC10A-+IN)") (class "Default")
      (node (ref "IC10") (pin "3") (pinfunction "+IN_3") (pintype "input"))
      (node (ref "R23") (pin "1") (pinfunction "1_1") (pintype "passive"))
    )
    (net (code "59") (name "Net-(IC10A--IN)") (class "Default")
      (node (ref "IC10") (pin "2") (pinfunction "-IN_2") (pintype "input"))
      (node (ref "R24") (pin "2") (pinfunction "2_2") (pintype "passive"))
      (node (ref "R25") (pin "1") (pinfunction "1_1") (pintype "passive"))
    )
    (net (code "60") (name "Net-(IC10A-OUT)") (class "Default")
      (node (ref "IC10") (pin "1") (pinfunction "OUT_1") (pintype "output"))
      (node (ref "R10") (pin "2") (pinfunction "2_2") (pintype "passive"))
      (node (ref "R24") (pin "1") (pinfunction "1_1") (pintype "passive"))
    )
    (net (code "61") (name "Net-(IC10B-+IN)") (class "Default")
      (node (ref "IC10") (pin "5") (pinfunction "+IN_5") (pintype "input"))
      (node (ref "R12") (pin "1") (pinfunction "1_1") (pintype "passive"))
    )
    (net (code "62") (name "Net-(IC10B--IN)") (class "Default")
      (node (ref "IC10") (pin "6") (pinfunction "-IN_6") (pintype "input"))
      (node (ref "R13") (pin "2") (pinfunction "2_2") (pintype "passive"))
      (node (ref "R14") (pin "1") (pinfunction "1_1") (pintype "passive"))
    )
    (net (code "63") (name "Net-(IC10B-OUT)") (class "Default")
      (node (ref "IC10") (pin "7") (pinfunction "OUT_7") (pintype "output"))
      (node (ref "R11") (pin "2") (pinfunction "2_2") (pintype "passive"))
      (node (ref "R13") (pin "1") (pinfunction "1_1") (pintype "passive"))
    )
    (net (code "64") (name "Net-(R1-Pad2)") (class "Default")
      (node (ref "R1") (pin "2") (pinfunction "2_2") (pintype "passive"))
      (node (ref "R3") (pin "1") (pinfunction "1_1") (pintype "passive"))
      (node (ref "X2") (pin "3") (pinfunction "3_3") (pintype "passive"))
    )
    (net (code "65") (name "Net-(R2-Pad1)") (class "Default")
      (node (ref "R2") (pin "1") (pinfunction "1_1") (pintype "passive"))
      (node (ref "X2") (pin "2") (pinfunction "2_2") (pintype "passive"))
    )
    (net (code "66") (name "Net-(R16-Pad2)") (class "Default")
      (node (ref "R16") (pin "2") (pinfunction "2_2") (pintype "passive"))
      (node (ref "X22") (pin "5") (pinfunction "5_5") (pintype "passive"))
    )
    (net (code "67") (name "Net-(R17-Pad1)") (class "Default")
      (node (ref "R17") (pin "1") (pinfunction "1_1") (pintype "passive"))
      (node (ref "X21") (pin "4") (pinfunction "4_4") (pintype "passive"))
    )
    (net (code "68") (name "Net-(R18-Pad1)") (class "Default")
      (node (ref "R18") (pin "1") (pinfunction "1_1") (pintype "passive"))
      (node (ref "X22") (pin "4") (pinfunction "4_4") (pintype "passive"))
    )
    (net (code "69") (name "Net-(U2-GAIN)") (class "Default")
      (node (ref "R7") (pin "1") (pinfunction "1_1") (pintype "passive"))
      (node (ref "U2") (pin "8") (pinfunction "GAIN_8") (pintype "passive"))
    )
    (net (code "70") (name "Net-(X11-2)") (class "Default")
      (node (ref "R10") (pin "1") (pinfunction "1_1") (pintype "passive"))
      (node (ref "X11") (pin "P$1") (pinfunction "2_P$1") (pintype "passive"))
    )
    (net (code "71") (name "Net-(X12-2)") (class "Default")
      (node (ref "R11") (pin "1") (pinfunction "1_1") (pintype "passive"))
      (node (ref "X12") (pin "P$1") (pinfunction "2_P$1") (pintype "passive"))
    )
    (net (code "72") (name "Net-(X13-2)") (class "Default")
      (node (ref "R15") (pin "1") (pinfunction "1_1") (pintype "passive"))
      (node (ref "X13") (pin "P$1") (pinfunction "2_P$1") (pintype "passive"))
    )
    (net (code "73") (name "Net-(X14-2)") (class "Default")
      (node (ref "R29") (pin "1") (pinfunction "1_1") (pintype "passive"))
      (node (ref "X14") (pin "P$1") (pinfunction "2_P$1") (pintype "passive"))
    )
    (net (code "74") (name "Net-(X15-2)") (class "Default")
      (node (ref "R33") (pin "1") (pinfunction "1_1") (pintype "passive"))
      (node (ref "X15") (pin "P$1") (pinfunction "2_P$1") (pintype "passive"))
    )
    (net (code "75") (name "Net-(X16-2)") (class "Default")
      (node (ref "R37") (pin "1") (pinfunction "1_1") (pintype "passive"))
      (node (ref "X16") (pin "P$1") (pinfunction "2_P$1") (pintype "passive"))
    )
    (net (code "76") (name "RST") (class "Default")
      (node (ref "C6") (pin "1") (pinfunction "1_1") (pintype "passive"))
      (node (ref "IC1") (pin "7") (pinfunction "NRST_7") (pintype "bidirectional"))
      (node (ref "J1") (pin "10") (pinfunction "~{RESET}_10") (pintype "bidirectional"))
      (node (ref "R4") (pin "1") (pinfunction "1_1") (pintype "passive"))
    )
    (net (code "77") (name "RST_DAC0") (class "Default")
      (node (ref "IC1") (pin "19") (pinfunction "PB1/TIM3_CH4/ADC_IN9/SDADC1_AIN5P/SDADC1_AIN6M_19") (pintype "bidirectional"))
      (node (ref "U2") (pin "17") (pinfunction "~{RESET}_17") (pintype "passive"))
    )
    (net (code "78") (name "RST_OLED") (class "Default")
      (node (ref "D1") (pin "RES") (pinfunction "RES_RES") (pintype "input"))
      (node (ref "IC1") (pin "18") (pinfunction "PB0/SPI1_MOSI/I2S1_SD/TIM3_CH3/ADC_IN8/SDADC1_AIN6P_18") (pintype "bidirectional"))
    )
    (net (code "79") (name "SCK") (class "Default")
      (node (ref "D1") (pin "CLK") (pinfunction "CLK_CLK") (pintype "input"))
      (node (ref "IC1") (pin "45") (pinfunction "PB8/SPI2_SCK/I2S2_CK/I2C1_SCL/USART3_TX/CAN_RX/TIM4_CH3_45") (pintype "bidirectional"))
      (node (ref "IC2") (pin "8") (pinfunction "SCLK_8") (pintype "passive"))
      (node (ref "U2") (pin "6") (pinfunction "SCLK_6") (pintype "passive"))
    )
    (net (code "80") (name "SDC_OLED") (class "Default")
      (node (ref "D1") (pin "SDC") (pinfunction "SDC_SDC") (pintype "bidirectional"))
      (node (ref "IC1") (pin "46") (pinfunction "PB9/SPI2_NSS/I2S2_WS/I2C1_SDA/USART3_RX/CAN_TX/TIM4_CH4_46") (pintype "bidirectional"))
    )
    (net (code "81") (name "SS_DAC0") (class "Default")
      (node (ref "IC1") (pin "40") (pinfunction "PB4/SPI1_MISO/I2S1_MCK/SPI3_MISO/I2S3_MCK/USART2_RX/TIM3_CH1/NJTRST_40") (pintype "bidirectional"))
      (node (ref "U2") (pin "5") (pinfunction "~{SYNC}_5") (pintype "passive"))
    )
    (net (code "82") (name "SS_DAC1") (class "Default")
      (node (ref "IC1") (pin "41") (pinfunction "PB5/SPI1_MOSI/I2S1_SD/SPI3_MOSI/I2S3_SD/I2C1_SMBAI/USART2_CK/TIM3_CH2_41") (pintype "bidirectional"))
      (node (ref "IC2") (pin "7") (pinfunction "SYNC_7") (pintype "passive"))
    )
    (net (code "83") (name "SS_OLED") (class "Default")
      (node (ref "D1") (pin "CCS") (pinfunction "CCS_CCS") (pintype "input"))
      (node (ref "IC1") (pin "20") (pinfunction "PB2/SDADC1_AIN4P/SDADC2_AIN6P_20") (pintype "bidirectional"))
      (node (ref "R5") (pin "1") (pinfunction "1_1") (pintype "passive"))
    )
    (net (code "84") (name "USB_PER_D_N") (class "Default")
      (node (ref "IC1") (pin "32") (pinfunction "PA11/SPI2_NSS/I2S2_WS/SPI1_NSS/I2S1_WS/USART1_CTS/CAN_RX/TIM4_CH1/TIM5_CH2_32") (pintype "bidirectional"))
      (node (ref "R2") (pin "2") (pinfunction "2_2") (pintype "passive"))
    )
    (net (code "85") (name "USB_PER_D_P") (class "Default")
      (node (ref "IC1") (pin "33") (pinfunction "PA12/SPI1_SCK/I2S1_CK/USART1_RTS/CAN_TX/TIM4_CH2/TIM5_CH3_33") (pintype "bidirectional"))
      (node (ref "R3") (pin "2") (pinfunction "2_2") (pintype "passive"))
    )
    (net (code "86") (name "unconnected-(IC1-PA6{slash}SPI1_MISO{slash}I2S1_MCK{slash}TIM3_CH1{slash}ADC_IN6{slash}DAC2_OUT1-Pad16)") (class "Default")
      (node (ref "IC1") (pin "16") (pinfunction "PA6/SPI1_MISO/I2S1_MCK/TIM3_CH1/ADC_IN6/DAC2_OUT1_16") (pintype "bidirectional"))
    )
    (net (code "87") (name "unconnected-(IC1-PA8{slash}SPI2_SCK{slash}I2S2_CK{slash}I2C2_SMBA{slash}USART1_CK{slash}TIM5_CH1-Pad29)") (class "Default")
      (node (ref "IC1") (pin "29") (pinfunction "PA8/SPI2_SCK/I2S2_CK/I2C2_SMBA/USART1_CK/TIM5_CH1_29") (pintype "bidirectional"))
    )
    (net (code "88") (name "unconnected-(IC1-PB6{slash}I2C1_SCL{slash}USART1_TX{slash}TIM4_CH1-Pad42)") (class "Default")
      (node (ref "IC1") (pin "42") (pinfunction "PB6/I2C1_SCL/USART1_TX/TIM4_CH1_42") (pintype "bidirectional"))
    )
    (net (code "89") (name "unconnected-(IC1-PB7{slash}I2C1_SDA{slash}USART1_RX{slash}TIM4_CH2-Pad43)") (class "Default")
      (node (ref "IC1") (pin "43") (pinfunction "PB7/I2C1_SDA/USART1_RX/TIM4_CH2_43") (pintype "bidirectional"))
    )
    (net (code "90") (name "unconnected-(IC1-PD8{slash}SPI2_SCK{slash}I2S2_CK{slash}USART3_TX{slash}SDADC3_AIN6P-Pad28)") (class "Default")
      (node (ref "IC1") (pin "28") (pinfunction "PD8/SPI2_SCK/I2S2_CK/USART3_TX/SDADC3_AIN6P_28") (pintype "bidirectional"))
    )
    (net (code "91") (name "unconnected-(IC1-PE9{slash}SDADC1_AIN7P{slash}SDADC1_AIN8M{slash}SDADC2_AIN7P{slash}SDADC2_AIN8M-Pad22)") (class "Default")
      (node (ref "IC1") (pin "22") (pinfunction "PE9/SDADC1_AIN7P/SDADC1_AIN8M/SDADC2_AIN7P/SDADC2_AIN8M_22") (pintype "bidirectional"))
    )
    (net (code "92") (name "unconnected-(IC1-PF6{slash}SPI1_MOSI{slash}I2S1_SD{slash}USART3_RTS{slash}TIM4_CH4{slash}I2C2_SCL-Pad35)") (class "Default")
      (node (ref "IC1") (pin "35") (pinfunction "PF6/SPI1_MOSI/I2S1_SD/USART3_RTS/TIM4_CH4/I2C2_SCL_35") (pintype "bidirectional"))
    )
    (net (code "93") (name "unconnected-(IC1-PF7{slash}I2C2_SDA{slash}USART2_CK-Pad36)") (class "Default")
      (node (ref "IC1") (pin "36") (pinfunction "PF7/I2C2_SDA/USART2_CK_36") (pintype "bidirectional"))
    )
    (net (code "94") (name "unconnected-(IC2-NC-Pad2)") (class "Default")
      (node (ref "IC2") (pin "2") (pinfunction "NC_2") (pintype "passive"))
    )
    (net (code "95") (name "unconnected-(IC2-NC_2-Pad13)") (class "Default")
      (node (ref "IC2") (pin "13") (pinfunction "NC_2_13") (pintype "passive"))
    )
    (net (code "96") (name "unconnected-(IC2-NC_3-Pad6)") (class "Default")
      (node (ref "IC2") (pin "6") (pinfunction "NC_3_6") (pintype "passive"))
    )
    (net (code "97") (name "unconnected-(IC2-NC_4-Pad12)") (class "Default")
      (node (ref "IC2") (pin "12") (pinfunction "NC_4_12") (pintype "passive"))
    )
    (net (code "98") (name "unconnected-(IC2-SDO-Pad16)") (class "Default")
      (node (ref "IC2") (pin "16") (pinfunction "SDO_16") (pintype "passive"))
    )
    (net (code "99") (name "unconnected-(IC8-COMP-Pad7)") (class "Default")
      (node (ref "IC8") (pin "7") (pinfunction "COMP_7") (pintype "bidirectional"))
    )
    (net (code "100") (name "unconnected-(IC8-DNC-Pad1)") (class "Default")
      (node (ref "IC8") (pin "1") (pinfunction "DNC_1") (pintype "no_connect"))
    )
    (net (code "101") (name "unconnected-(IC8-DNC2-Pad8)") (class "Default")
      (node (ref "IC8") (pin "8") (pinfunction "DNC2_8") (pintype "no_connect"))
    )
    (net (code "102") (name "unconnected-(IC8-NIC-Pad3)") (class "Default")
      (node (ref "IC8") (pin "3") (pinfunction "NIC_3") (pintype "no_connect"))
    )
    (net (code "103") (name "unconnected-(IC8-TRIM-Pad5)") (class "Default")
      (node (ref "IC8") (pin "5") (pinfunction "TRIM_5") (pintype "bidirectional"))
    )
    (net (code "104") (name "unconnected-(IC9-COMP-Pad7)") (class "Default")
      (node (ref "IC9") (pin "7") (pinfunction "COMP_7") (pintype "bidirectional"))
    )
    (net (code "105") (name "unconnected-(IC9-DNC-Pad1)") (class "Default")
      (node (ref "IC9") (pin "1") (pinfunction "DNC_1") (pintype "no_connect"))
    )
    (net (code "106") (name "unconnected-(IC9-DNC2-Pad8)") (class "Default")
      (node (ref "IC9") (pin "8") (pinfunction "DNC2_8") (pintype "no_connect"))
    )
    (net (code "107") (name "unconnected-(IC9-NIC-Pad3)") (class "Default")
      (node (ref "IC9") (pin "3") (pinfunction "NIC_3") (pintype "no_connect"))
    )
    (net (code "108") (name "unconnected-(IC9-TRIM-Pad5)") (class "Default")
      (node (ref "IC9") (pin "5") (pinfunction "TRIM_5") (pintype "bidirectional"))
    )
    (net (code "109") (name "unconnected-(J1-KEY-Pad7)") (class "Default")
      (node (ref "J1") (pin "7") (pinfunction "KEY_7") (pintype "bidirectional"))
    )
    (net (code "110") (name "unconnected-(U$1-Pad1)") (class "Default")
      (node (ref "U$1") (pin "1") (pinfunction "1_1") (pintype "bidirectional"))
    )
    (net (code "111") (name "unconnected-(U$1-Pad2)") (class "Default")
      (node (ref "U$1") (pin "2") (pinfunction "2_2") (pintype "bidirectional"))
    )
    (net (code "112") (name "unconnected-(U2-SDO-Pad16)") (class "Default")
      (node (ref "U2") (pin "16") (pinfunction "SDO_16") (pintype "passive"))
    )
    (net (code "113") (name "unconnected-(X2-Pad1)") (class "Default")
      (node (ref "X2") (pin "1") (pinfunction "1_1") (pintype "passive"))
    )
    (net (code "114") (name "unconnected-(X3-3-PadP$2)") (class "Default")
      (node (ref "X3") (pin "P$2") (pinfunction "3_P$2") (pintype "passive"))
    )
    (net (code "115") (name "unconnected-(X4-3-PadP$2)") (class "Default")
      (node (ref "X4") (pin "P$2") (pinfunction "3_P$2") (pintype "passive"))
    )
    (net (code "116") (name "unconnected-(X5-3-PadP$2)") (class "Default")
      (node (ref "X5") (pin "P$2") (pinfunction "3_P$2") (pintype "passive"))
    )
    (net (code "117") (name "unconnected-(X6-3-PadP$2)") (class "Default")
      (node (ref "X6") (pin "P$2") (pinfunction "3_P$2") (pintype "passive"))
    )
    (net (code "118") (name "unconnected-(X7-3-PadP$2)") (class "Default")
      (node (ref "X7") (pin "P$2") (pinfunction "3_P$2") (pintype "passive"))
    )
    (net (code "119") (name "unconnected-(X8-3-PadP$2)") (class "Default")
      (node (ref "X8") (pin "P$2") (pinfunction "3_P$2") (pintype "passive"))
    )
    (net (code "120") (name "unconnected-(X9-3-PadP$2)") (class "Default")
      (node (ref "X9") (pin "P$2") (pinfunction "3_P$2") (pintype "passive"))
    )
    (net (code "121") (name "unconnected-(X10-3-PadP$2)") (class "Default")
      (node (ref "X10") (pin "P$2") (pinfunction "3_P$2") (pintype "passive"))
    )
    (net (code "122") (name "unconnected-(X11-3-PadP$2)") (class "Default")
      (node (ref "X11") (pin "P$2") (pinfunction "3_P$2") (pintype "passive"))
    )
    (net (code "123") (name "unconnected-(X12-3-PadP$2)") (class "Default")
      (node (ref "X12") (pin "P$2") (pinfunction "3_P$2") (pintype "passive"))
    )
    (net (code "124") (name "unconnected-(X13-3-PadP$2)") (class "Default")
      (node (ref "X13") (pin "P$2") (pinfunction "3_P$2") (pintype "passive"))
    )
    (net (code "125") (name "unconnected-(X14-3-PadP$2)") (class "Default")
      (node (ref "X14") (pin "P$2") (pinfunction "3_P$2") (pintype "passive"))
    )
    (net (code "126") (name "unconnected-(X15-3-PadP$2)") (class "Default")
      (node (ref "X15") (pin "P$2") (pinfunction "3_P$2") (pintype "passive"))
    )
    (net (code "127") (name "unconnected-(X16-3-PadP$2)") (class "Default")
      (node (ref "X16") (pin "P$2") (pinfunction "3_P$2") (pintype "passive"))
    )
    (net (code "128") (name "unconnected-(X17-3-PadP$2)") (class "Default")
      (node (ref "X17") (pin "P$2") (pinfunction "3_P$2") (pintype "passive"))
    )
    (net (code "129") (name "unconnected-(X18-3-PadP$2)") (class "Default")
      (node (ref "X18") (pin "P$2") (pinfunction "3_P$2") (pintype "passive"))
    )
    (net (code "130") (name "unconnected-(X19-3-PadP$2)") (class "Default")
      (node (ref "X19") (pin "P$2") (pinfunction "3_P$2") (pintype "passive"))
    )
    (net (code "131") (name "unconnected-(X20-3-PadP$2)") (class "Default")
      (node (ref "X20") (pin "P$2") (pinfunction "3_P$2") (pintype "passive"))
    )
    (net (code "132") (name "unconnected-(X21-Pad1)") (class "Default")
      (node (ref "X21") (pin "1") (pinfunction "1_1") (pintype "passive"))
    )
    (net (code "133") (name "unconnected-(X21-Pad2)") (class "Default")
      (node (ref "X21") (pin "2") (pinfunction "2_2") (pintype "passive"))
    )
    (net (code "134") (name "unconnected-(X21-Pad3)") (class "Default")
      (node (ref "X21") (pin "3") (pinfunction "3_3") (pintype "passive"))
    )
    (net (code "135") (name "unconnected-(X22-Pad1)") (class "Default")
      (node (ref "X22") (pin "1") (pinfunction "1_1") (pintype "passive"))
    )
    (net (code "136") (name "unconnected-(X22-Pad3)") (class "Default")
      (node (ref "X22") (pin "3") (pinfunction "3_3") (pintype "passive"))
    )
  )
)
